# LEDs_Switches.net
KiCad netlist of a schematic drawn in Altium Designer
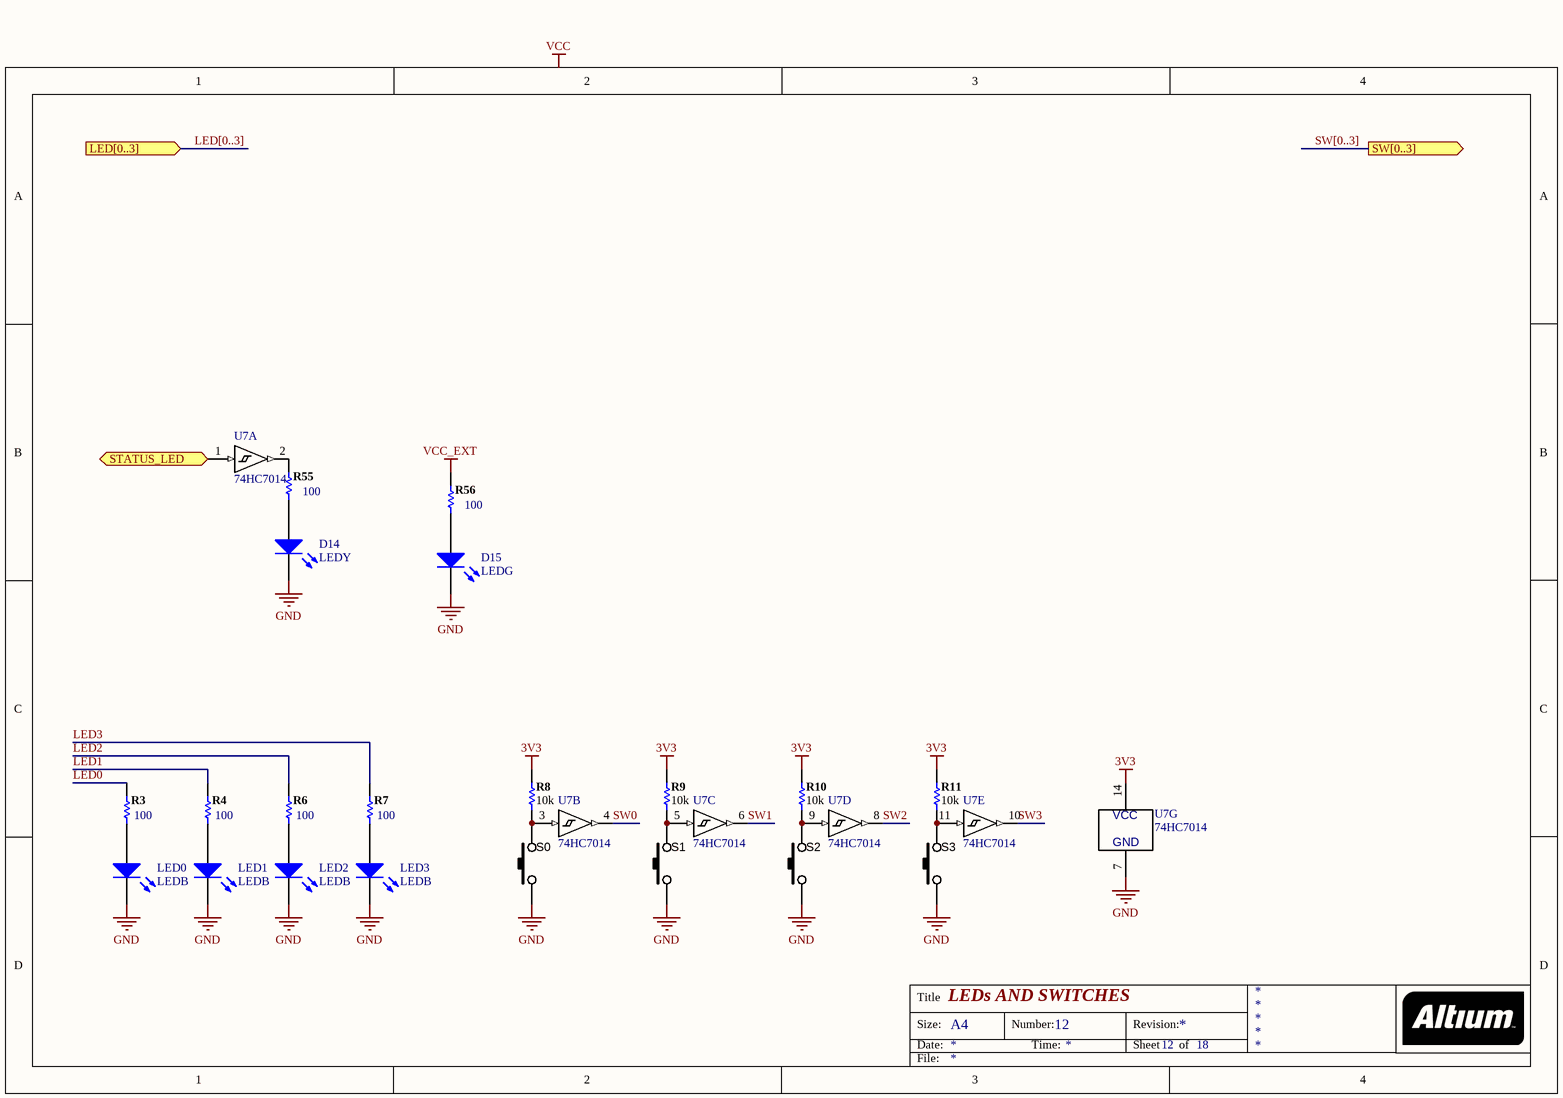
[diagram p0: LEDs_Switches.SchDoc]

(export (version "E")
  (design (tool "Eeschema 10.0.6"))
  (components
    (comp (ref "D14")
      (value "LEDY")
      (footprint "LED-0805-K")
      (description "Typical RED, GREEN, YELLOW, AMBER GaAs LED")
      (fields (field (name "PUBLISHER") "Altium Limited"))
      (libsource (lib "Miscellaneous Devices") (part "LED2"))
    )
    (comp (ref "D15")
      (value "LEDG")
      (footprint "LED-0805-K")
      (description "Typical RED, GREEN, YELLOW, AMBER GaAs LED")
      (fields (field (name "PUBLISHER") "Altium Limited"))
      (libsource (lib "Miscellaneous Devices") (part "LED2"))
    )
    (comp (ref "LED0")
      (value "LEDB")
      (footprint "LED-0805-K")
      (description "Typical BLUE GaAs LED")
      (fields (field (name "PUBLISHER") "Altium Limited"))
      (libsource (lib "Miscellaneous Devices") (part "LED2"))
    )
    (comp (ref "LED1")
      (value "LEDB")
      (footprint "LED-0805-K")
      (description "Typical BLUE GaAs LED")
      (fields (field (name "PUBLISHER") "Altium Limited"))
      (libsource (lib "Miscellaneous Devices") (part "LED2"))
    )
    (comp (ref "LED2")
      (value "LEDB")
      (footprint "LED-0805-K")
      (description "Typical BLUE GaAs LED")
      (fields (field (name "PUBLISHER") "Altium Limited"))
      (libsource (lib "Miscellaneous Devices") (part "LED2"))
    )
    (comp (ref "LED3")
      (value "LEDB")
      (footprint "LED-0805-K")
      (description "Typical BLUE GaAs LED")
      (fields (field (name "PUBLISHER") "Altium Limited"))
      (libsource (lib "Miscellaneous Devices") (part "LED2"))
    )
    (comp (ref "R3")
      (value "100")
      (footprint "0805R-100")
      (fields (field (name "TOLERANCE") "1 %"))
      (libsource (lib "AltiumDesignLibrary") (part "RES"))
    )
    (comp (ref "R4")
      (value "100")
      (footprint "0805R-100")
      (fields (field (name "TOLERANCE") "1 %"))
      (libsource (lib "AltiumDesignLibrary") (part "RES"))
    )
    (comp (ref "R6")
      (value "100")
      (footprint "0805R-100")
      (fields (field (name "TOLERANCE") "1 %"))
      (libsource (lib "AltiumDesignLibrary") (part "RES"))
    )
    (comp (ref "R7")
      (value "100")
      (footprint "0805R-100")
      (fields (field (name "TOLERANCE") "1 %"))
      (libsource (lib "AltiumDesignLibrary") (part "RES"))
    )
    (comp (ref "R8")
      (value "10k")
      (footprint "0805R-10K")
      (fields (field (name "TOLERANCE") "1 %"))
      (libsource (lib "AltiumDesignLibrary") (part "RES"))
    )
    (comp (ref "R9")
      (value "10k")
      (footprint "0805R-10K")
      (fields (field (name "TOLERANCE") "1 %"))
      (libsource (lib "AltiumDesignLibrary") (part "RES"))
    )
    (comp (ref "R10")
      (value "10k")
      (footprint "0805R-10K")
      (fields (field (name "TOLERANCE") "1 %"))
      (libsource (lib "AltiumDesignLibrary") (part "RES"))
    )
    (comp (ref "R11")
      (value "10k")
      (footprint "0805R-10K")
      (fields (field (name "TOLERANCE") "1 %"))
      (libsource (lib "AltiumDesignLibrary") (part "RES"))
    )
    (comp (ref "R55")
      (value "100")
      (footprint "0805R-100")
      (fields (field (name "TOLERANCE") "1 %"))
      (libsource (lib "AltiumDesignLibrary") (part "RES"))
    )
    (comp (ref "R56")
      (value "100")
      (footprint "0805R-100")
      (fields (field (name "TOLERANCE") "1 %"))
      (libsource (lib "AltiumDesignLibrary") (part "RES"))
    )
    (comp (ref "S0")
      (value "EVQ-PQHB55")
      (footprint "TACT-SWITCH-TS1150")
      (description "Low-profile captive tact switch")
      (libsource (lib "PBL - Switches") (part "SW_EVQ-PQHB55"))
    )
    (comp (ref "S1")
      (value "EVQ-PQHB55")
      (footprint "TACT-SWITCH-TS1150")
      (description "Low-profile captive tact switch")
      (libsource (lib "PBL - Switches") (part "SW_EVQ-PQHB55"))
    )
    (comp (ref "S2")
      (value "EVQ-PQHB55")
      (footprint "TACT-SWITCH-TS1150")
      (description "Low-profile captive tact switch")
      (libsource (lib "PBL - Switches") (part "SW_EVQ-PQHB55"))
    )
    (comp (ref "S3")
      (value "EVQ-PQHB55")
      (footprint "TACT-SWITCH-TS1150")
      (description "Low-profile captive tact switch")
      (libsource (lib "PBL - Switches") (part "SW_EVQ-PQHB55"))
    )
    (comp (ref "U7")
      (value "74HC7014")
      (footprint "SO14")
      (description "IC, Hex Schmitttrigger Buffer, SO-14")
      (libsource (lib "vh_altium_library") (part "74HC7014"))
    )
  )
  (nets
    (net (code "1") (name "/LED0") (class "Default")
      (node (ref "R3") (pin "2") (pinfunction "2_2") (pintype "passive"))
    )
    (net (code "2") (name "/LED1") (class "Default")
      (node (ref "R4") (pin "2") (pinfunction "2_2") (pintype "passive"))
    )
    (net (code "3") (name "/LED2") (class "Default")
      (node (ref "R6") (pin "2") (pinfunction "2_2") (pintype "passive"))
    )
    (net (code "4") (name "/LED3") (class "Default")
      (node (ref "R7") (pin "2") (pinfunction "2_2") (pintype "passive"))
    )
    (net (code "6") (name "/STATUS_LED") (class "Default")
      (node (ref "U7") (pin "1") (pinfunction "A_1") (pintype "input"))
    )
    (net (code "7") (name "/SW0") (class "Default")
      (node (ref "U7") (pin "4") (pinfunction "Y_4") (pintype "output"))
    )
    (net (code "8") (name "/SW1") (class "Default")
      (node (ref "U7") (pin "6") (pinfunction "Y_6") (pintype "output"))
    )
    (net (code "9") (name "/SW2") (class "Default")
      (node (ref "U7") (pin "8") (pinfunction "Y_8") (pintype "output"))
    )
    (net (code "10") (name "/SW3") (class "Default")
      (node (ref "U7") (pin "10") (pinfunction "Y_10") (pintype "output"))
    )
    (net (code "12") (name "3V3") (class "Default")
      (node (ref "R10") (pin "2") (pinfunction "2_2") (pintype "passive"))
      (node (ref "R11") (pin "2") (pinfunction "2_2") (pintype "passive"))
      (node (ref "R8") (pin "2") (pinfunction "2_2") (pintype "passive"))
      (node (ref "R9") (pin "2") (pinfunction "2_2") (pintype "passive"))
      (node (ref "U7") (pin "14") (pinfunction "VCC_14") (pintype "passive"))
    )
    (net (code "13") (name "GND") (class "Default")
      (node (ref "D14") (pin "K") (pinfunction "K_K") (pintype "passive"))
      (node (ref "D15") (pin "K") (pinfunction "K_K") (pintype "passive"))
      (node (ref "LED0") (pin "K") (pinfunction "K_K") (pintype "passive"))
      (node (ref "LED1") (pin "K") (pinfunction "K_K") (pintype "passive"))
      (node (ref "LED2") (pin "K") (pinfunction "K_K") (pintype "passive"))
      (node (ref "LED3") (pin "K") (pinfunction "K_K") (pintype "passive"))
      (node (ref "S0") (pin "1") (pintype "passive"))
      (node (ref "S1") (pin "1") (pintype "passive"))
      (node (ref "S2") (pin "1") (pintype "passive"))
      (node (ref "S3") (pin "1") (pintype "passive"))
      (node (ref "U7") (pin "7") (pinfunction "GND_7") (pintype "passive"))
    )
    (net (code "14") (name "Net-(D14-PadA)") (class "Default")
      (node (ref "D14") (pin "A") (pinfunction "A_A") (pintype "passive"))
      (node (ref "R55") (pin "1") (pinfunction "1_1") (pintype "passive"))
    )
    (net (code "15") (name "Net-(D15-PadA)") (class "Default")
      (node (ref "D15") (pin "A") (pinfunction "A_A") (pintype "passive"))
      (node (ref "R56") (pin "1") (pinfunction "1_1") (pintype "passive"))
    )
    (net (code "16") (name "Net-(LED0-PadA)") (class "Default")
      (node (ref "LED0") (pin "A") (pinfunction "A_A") (pintype "passive"))
      (node (ref "R3") (pin "1") (pinfunction "1_1") (pintype "passive"))
    )
    (net (code "17") (name "Net-(LED1-PadA)") (class "Default")
      (node (ref "LED1") (pin "A") (pinfunction "A_A") (pintype "passive"))
      (node (ref "R4") (pin "1") (pinfunction "1_1") (pintype "passive"))
    )
    (net (code "18") (name "Net-(LED2-PadA)") (class "Default")
      (node (ref "LED2") (pin "A") (pinfunction "A_A") (pintype "passive"))
      (node (ref "R6") (pin "1") (pinfunction "1_1") (pintype "passive"))
    )
    (net (code "19") (name "Net-(LED3-PadA)") (class "Default")
      (node (ref "LED3") (pin "A") (pinfunction "A_A") (pintype "passive"))
      (node (ref "R7") (pin "1") (pinfunction "1_1") (pintype "passive"))
    )
    (net (code "20") (name "Net-(U7A-Y)") (class "Default")
      (node (ref "R55") (pin "2") (pinfunction "2_2") (pintype "passive"))
      (node (ref "U7") (pin "2") (pinfunction "Y_2") (pintype "output"))
    )
    (net (code "21") (name "Net-(U7B-A)") (class "Default")
      (node (ref "R8") (pin "1") (pinfunction "1_1") (pintype "passive"))
      (node (ref "S0") (pin "2") (pintype "passive"))
      (node (ref "U7") (pin "3") (pinfunction "A_3") (pintype "input"))
    )
    (net (code "22") (name "Net-(U7C-A)") (class "Default")
      (node (ref "R9") (pin "1") (pinfunction "1_1") (pintype "passive"))
      (node (ref "S1") (pin "2") (pintype "passive"))
      (node (ref "U7") (pin "5") (pinfunction "A_5") (pintype "input"))
    )
    (net (code "23") (name "Net-(U7D-A)") (class "Default")
      (node (ref "R10") (pin "1") (pinfunction "1_1") (pintype "passive"))
      (node (ref "S2") (pin "2") (pintype "passive"))
      (node (ref "U7") (pin "9") (pinfunction "A_9") (pintype "input"))
    )
    (net (code "24") (name "Net-(U7E-A)") (class "Default")
      (node (ref "R11") (pin "1") (pinfunction "1_1") (pintype "passive"))
      (node (ref "S3") (pin "2") (pintype "passive"))
      (node (ref "U7") (pin "11") (pinfunction "A_11") (pintype "input"))
    )
    (net (code "26") (name "VCC_EXT") (class "Default")
      (node (ref "R56") (pin "2") (pinfunction "2_2") (pintype "passive"))
    )
  )
)
